# custom_line_V1_mux6.net
KiCad netlist of a schematic drawn in Altium Designer
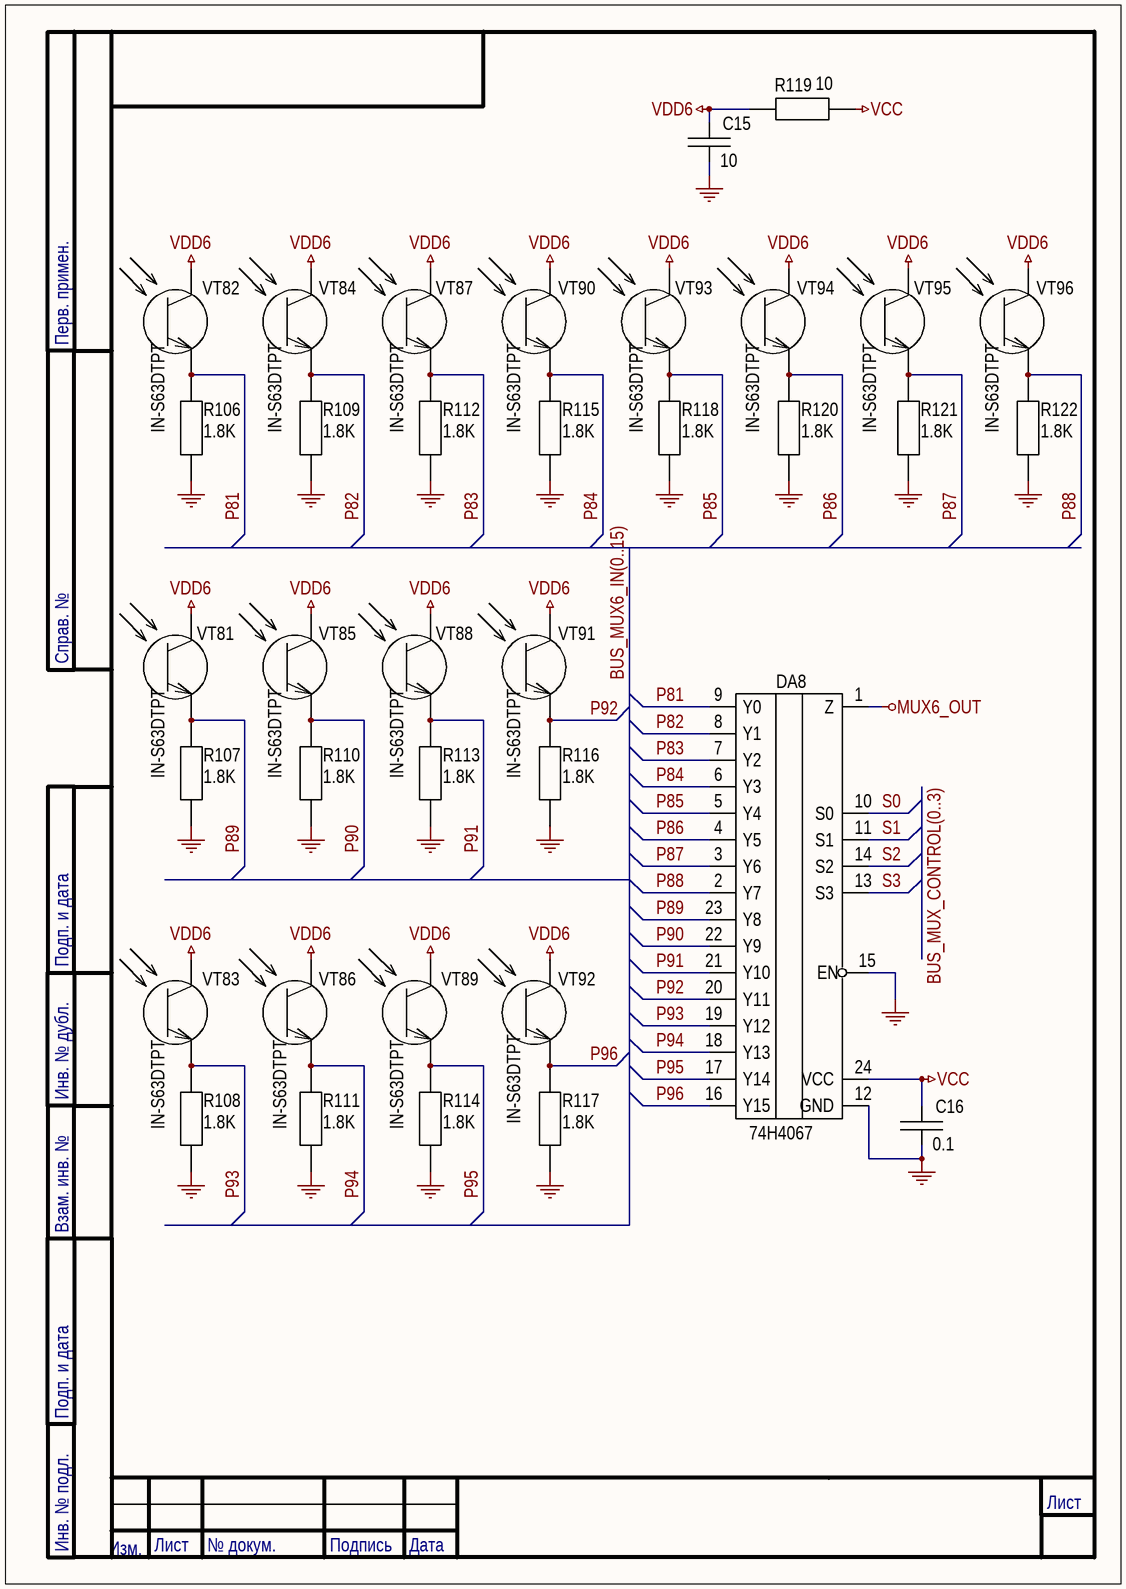
[diagram p0: custom_line_V1_mux6.SchDoc]

(export (version "E")
  (design (tool "Eeschema 10.0.6"))
  (components
    (comp (ref "C15") (value "10") (footprint "CC_0805") (libsource (lib "my_discrete_new") (part "C")))
    (comp (ref "C16") (value "0.1") (footprint "CC_0603") (libsource (lib "my_discrete_new") (part "C")))
    (comp (ref "DA8")
      (value "74HC4067")
      (footprint "TSSOP-24")
      (description "74HC4067PW")
      (fields (field (name "TYPE") "74H4067"))
      (libsource (lib "my_microschems_new") (part "74HCT4067"))
    )
    (comp (ref "R106")
      (value "1.8K")
      (footprint "RC_0603_SMALL")
      (fields (field (name "POWER") "0.125W"))
      (libsource (lib "my_discrete_new") (part "R"))
    )
    (comp (ref "R107")
      (value "1.8K")
      (footprint "RC_0603_SMALL")
      (fields (field (name "POWER") "0.125W"))
      (libsource (lib "my_discrete_new") (part "R"))
    )
    (comp (ref "R108")
      (value "1.8K")
      (footprint "RC_0603_SMALL")
      (fields (field (name "POWER") "0.125W"))
      (libsource (lib "my_discrete_new") (part "R"))
    )
    (comp (ref "R109")
      (value "1.8K")
      (footprint "RC_0603_SMALL")
      (fields (field (name "POWER") "0.125W"))
      (libsource (lib "my_discrete_new") (part "R"))
    )
    (comp (ref "R110")
      (value "1.8K")
      (footprint "RC_0603_SMALL")
      (fields (field (name "POWER") "0.125W"))
      (libsource (lib "my_discrete_new") (part "R"))
    )
    (comp (ref "R111")
      (value "1.8K")
      (footprint "RC_0603_SMALL")
      (fields (field (name "POWER") "0.125W"))
      (libsource (lib "my_discrete_new") (part "R"))
    )
    (comp (ref "R112")
      (value "1.8K")
      (footprint "RC_0603_SMALL")
      (fields (field (name "POWER") "0.125W"))
      (libsource (lib "my_discrete_new") (part "R"))
    )
    (comp (ref "R113")
      (value "1.8K")
      (footprint "RC_0603_SMALL")
      (fields (field (name "POWER") "0.125W"))
      (libsource (lib "my_discrete_new") (part "R"))
    )
    (comp (ref "R114")
      (value "1.8K")
      (footprint "RC_0603_SMALL")
      (fields (field (name "POWER") "0.125W"))
      (libsource (lib "my_discrete_new") (part "R"))
    )
    (comp (ref "R115")
      (value "1.8K")
      (footprint "RC_0603_SMALL")
      (fields (field (name "POWER") "0.125W"))
      (libsource (lib "my_discrete_new") (part "R"))
    )
    (comp (ref "R116")
      (value "1.8K")
      (footprint "RC_0603_SMALL")
      (fields (field (name "POWER") "0.125W"))
      (libsource (lib "my_discrete_new") (part "R"))
    )
    (comp (ref "R117")
      (value "1.8K")
      (footprint "RC_0603_SMALL")
      (fields (field (name "POWER") "0.125W"))
      (libsource (lib "my_discrete_new") (part "R"))
    )
    (comp (ref "R118")
      (value "1.8K")
      (footprint "RC_0603_SMALL")
      (fields (field (name "POWER") "0.125W"))
      (libsource (lib "my_discrete_new") (part "R"))
    )
    (comp (ref "R119")
      (value "10")
      (footprint "RC_0603_SMALL")
      (fields (field (name "POWER") "0.125W"))
      (libsource (lib "my_discrete_new") (part "R"))
    )
    (comp (ref "R120")
      (value "1.8K")
      (footprint "RC_0603_SMALL")
      (fields (field (name "POWER") "0.125W"))
      (libsource (lib "my_discrete_new") (part "R"))
    )
    (comp (ref "R121")
      (value "1.8K")
      (footprint "RC_0603_SMALL")
      (fields (field (name "POWER") "0.125W"))
      (libsource (lib "my_discrete_new") (part "R"))
    )
    (comp (ref "R122")
      (value "1.8K")
      (footprint "RC_0603_SMALL")
      (fields (field (name "POWER") "0.125W"))
      (libsource (lib "my_discrete_new") (part "R"))
    )
    (comp (ref "VT81")
      (value "IN-S63DTPT")
      (footprint "LED_0603")
      (description "Phototransistor (Inolux)")
      (libsource (lib "my_discrete_new") (part "phototransistor"))
    )
    (comp (ref "VT82")
      (value "IN-S63DTPT")
      (footprint "LED_0603")
      (description "Phototransistor (Inolux)")
      (libsource (lib "my_discrete_new") (part "phototransistor"))
    )
    (comp (ref "VT83")
      (value "IN-S63DTPT")
      (footprint "LED_0603")
      (description "Phototransistor (Inolux)")
      (libsource (lib "my_discrete_new") (part "phototransistor"))
    )
    (comp (ref "VT84")
      (value "IN-S63DTPT")
      (footprint "LED_0603")
      (description "Phototransistor (Inolux)")
      (libsource (lib "my_discrete_new") (part "phototransistor"))
    )
    (comp (ref "VT85")
      (value "IN-S63DTPT")
      (footprint "LED_0603")
      (description "Phototransistor (Inolux)")
      (libsource (lib "my_discrete_new") (part "phototransistor"))
    )
    (comp (ref "VT86")
      (value "IN-S63DTPT")
      (footprint "LED_0603")
      (description "Phototransistor (Inolux)")
      (libsource (lib "my_discrete_new") (part "phototransistor"))
    )
    (comp (ref "VT87")
      (value "IN-S63DTPT")
      (footprint "LED_0603")
      (description "Phototransistor (Inolux)")
      (libsource (lib "my_discrete_new") (part "phototransistor"))
    )
    (comp (ref "VT88")
      (value "IN-S63DTPT")
      (footprint "LED_0603")
      (description "Phototransistor (Inolux)")
      (libsource (lib "my_discrete_new") (part "phototransistor"))
    )
    (comp (ref "VT89")
      (value "IN-S63DTPT")
      (footprint "LED_0603")
      (description "Phototransistor (Inolux)")
      (libsource (lib "my_discrete_new") (part "phototransistor"))
    )
    (comp (ref "VT90")
      (value "IN-S63DTPT")
      (footprint "LED_0603")
      (description "Phototransistor (Inolux)")
      (libsource (lib "my_discrete_new") (part "phototransistor"))
    )
    (comp (ref "VT91")
      (value "IN-S63DTPT")
      (footprint "LED_0603")
      (description "Phototransistor (Inolux)")
      (libsource (lib "my_discrete_new") (part "phototransistor"))
    )
    (comp (ref "VT92")
      (value "IN-S63DTPT")
      (footprint "LED_0603")
      (description "Phototransistor (Inolux)")
      (libsource (lib "my_discrete_new") (part "phototransistor"))
    )
    (comp (ref "VT93")
      (value "IN-S63DTPT")
      (footprint "LED_0603")
      (description "Phototransistor (Inolux)")
      (libsource (lib "my_discrete_new") (part "phototransistor"))
    )
    (comp (ref "VT94")
      (value "IN-S63DTPT")
      (footprint "LED_0603")
      (description "Phototransistor (Inolux)")
      (libsource (lib "my_discrete_new") (part "phototransistor"))
    )
    (comp (ref "VT95")
      (value "IN-S63DTPT")
      (footprint "LED_0603")
      (description "Phototransistor (Inolux)")
      (libsource (lib "my_discrete_new") (part "phototransistor"))
    )
    (comp (ref "VT96")
      (value "IN-S63DTPT")
      (footprint "LED_0603")
      (description "Phototransistor (Inolux)")
      (libsource (lib "my_discrete_new") (part "phototransistor"))
    )
  )
  (nets
    (net (code "3") (name "/P81") (class "Default")
      (node (ref "DA8") (pin "9") (pinfunction "Y0_9") (pintype "passive"))
      (node (ref "R106") (pin "2") (pinfunction "2_2") (pintype "passive"))
      (node (ref "VT82") (pin "2") (pinfunction "E_2") (pintype "passive"))
    )
    (net (code "4") (name "/P82") (class "Default")
      (node (ref "DA8") (pin "8") (pinfunction "Y1_8") (pintype "passive"))
      (node (ref "R109") (pin "2") (pinfunction "2_2") (pintype "passive"))
      (node (ref "VT84") (pin "2") (pinfunction "E_2") (pintype "passive"))
    )
    (net (code "5") (name "/P83") (class "Default")
      (node (ref "DA8") (pin "7") (pinfunction "Y2_7") (pintype "passive"))
      (node (ref "R112") (pin "2") (pinfunction "2_2") (pintype "passive"))
      (node (ref "VT87") (pin "2") (pinfunction "E_2") (pintype "passive"))
    )
    (net (code "6") (name "/P84") (class "Default")
      (node (ref "DA8") (pin "6") (pinfunction "Y3_6") (pintype "passive"))
      (node (ref "R115") (pin "2") (pinfunction "2_2") (pintype "passive"))
      (node (ref "VT90") (pin "2") (pinfunction "E_2") (pintype "passive"))
    )
    (net (code "7") (name "/P85") (class "Default")
      (node (ref "DA8") (pin "5") (pinfunction "Y4_5") (pintype "passive"))
      (node (ref "R118") (pin "2") (pinfunction "2_2") (pintype "passive"))
      (node (ref "VT93") (pin "2") (pinfunction "E_2") (pintype "passive"))
    )
    (net (code "8") (name "/P86") (class "Default")
      (node (ref "DA8") (pin "4") (pinfunction "Y5_4") (pintype "passive"))
      (node (ref "R120") (pin "2") (pinfunction "2_2") (pintype "passive"))
      (node (ref "VT94") (pin "2") (pinfunction "E_2") (pintype "passive"))
    )
    (net (code "9") (name "/P87") (class "Default")
      (node (ref "DA8") (pin "3") (pinfunction "Y6_3") (pintype "passive"))
      (node (ref "R121") (pin "2") (pinfunction "2_2") (pintype "passive"))
      (node (ref "VT95") (pin "2") (pinfunction "E_2") (pintype "passive"))
    )
    (net (code "10") (name "/P88") (class "Default")
      (node (ref "DA8") (pin "2") (pinfunction "Y7_2") (pintype "passive"))
      (node (ref "R122") (pin "2") (pinfunction "2_2") (pintype "passive"))
      (node (ref "VT96") (pin "2") (pinfunction "E_2") (pintype "passive"))
    )
    (net (code "11") (name "/P89") (class "Default")
      (node (ref "DA8") (pin "23") (pinfunction "Y8_23") (pintype "passive"))
      (node (ref "R107") (pin "2") (pinfunction "2_2") (pintype "passive"))
      (node (ref "VT81") (pin "2") (pinfunction "E_2") (pintype "passive"))
    )
    (net (code "12") (name "/P90") (class "Default")
      (node (ref "DA8") (pin "22") (pinfunction "Y9_22") (pintype "passive"))
      (node (ref "R110") (pin "2") (pinfunction "2_2") (pintype "passive"))
      (node (ref "VT85") (pin "2") (pinfunction "E_2") (pintype "passive"))
    )
    (net (code "13") (name "/P91") (class "Default")
      (node (ref "DA8") (pin "21") (pinfunction "Y10_21") (pintype "passive"))
      (node (ref "R113") (pin "2") (pinfunction "2_2") (pintype "passive"))
      (node (ref "VT88") (pin "2") (pinfunction "E_2") (pintype "passive"))
    )
    (net (code "14") (name "/P92") (class "Default")
      (node (ref "DA8") (pin "20") (pinfunction "Y11_20") (pintype "passive"))
      (node (ref "R116") (pin "2") (pinfunction "2_2") (pintype "passive"))
      (node (ref "VT91") (pin "2") (pinfunction "E_2") (pintype "passive"))
    )
    (net (code "15") (name "/P93") (class "Default")
      (node (ref "DA8") (pin "19") (pinfunction "Y12_19") (pintype "passive"))
      (node (ref "R108") (pin "2") (pinfunction "2_2") (pintype "passive"))
      (node (ref "VT83") (pin "2") (pinfunction "E_2") (pintype "passive"))
    )
    (net (code "16") (name "/P94") (class "Default")
      (node (ref "DA8") (pin "18") (pinfunction "Y13_18") (pintype "passive"))
      (node (ref "R111") (pin "2") (pinfunction "2_2") (pintype "passive"))
      (node (ref "VT86") (pin "2") (pinfunction "E_2") (pintype "passive"))
    )
    (net (code "17") (name "/P95") (class "Default")
      (node (ref "DA8") (pin "17") (pinfunction "Y14_17") (pintype "passive"))
      (node (ref "R114") (pin "2") (pinfunction "2_2") (pintype "passive"))
      (node (ref "VT89") (pin "2") (pinfunction "E_2") (pintype "passive"))
    )
    (net (code "18") (name "/P96") (class "Default")
      (node (ref "DA8") (pin "16") (pinfunction "Y15_16") (pintype "passive"))
      (node (ref "R117") (pin "2") (pinfunction "2_2") (pintype "passive"))
      (node (ref "VT92") (pin "2") (pinfunction "E_2") (pintype "passive"))
    )
    (net (code "19") (name "/S0") (class "Default")
      (node (ref "DA8") (pin "10") (pinfunction "S0_10") (pintype "passive"))
    )
    (net (code "20") (name "/S1") (class "Default")
      (node (ref "DA8") (pin "11") (pinfunction "S1_11") (pintype "passive"))
    )
    (net (code "21") (name "/S2") (class "Default")
      (node (ref "DA8") (pin "14") (pinfunction "S2_14") (pintype "passive"))
    )
    (net (code "22") (name "/S3") (class "Default")
      (node (ref "DA8") (pin "13") (pinfunction "S3_13") (pintype "passive"))
    )
    (net (code "25") (name "GND") (class "Default")
      (node (ref "C15") (pin "1") (pinfunction "1_1") (pintype "passive"))
      (node (ref "C16") (pin "1") (pinfunction "1_1") (pintype "passive"))
      (node (ref "DA8") (pin "12") (pinfunction "GND_12") (pintype "power_in"))
      (node (ref "DA8") (pin "15") (pinfunction "EN_15") (pintype "passive"))
      (node (ref "R106") (pin "1") (pinfunction "1_1") (pintype "passive"))
      (node (ref "R107") (pin "1") (pinfunction "1_1") (pintype "passive"))
      (node (ref "R108") (pin "1") (pinfunction "1_1") (pintype "passive"))
      (node (ref "R109") (pin "1") (pinfunction "1_1") (pintype "passive"))
      (node (ref "R110") (pin "1") (pinfunction "1_1") (pintype "passive"))
      (node (ref "R111") (pin "1") (pinfunction "1_1") (pintype "passive"))
      (node (ref "R112") (pin "1") (pinfunction "1_1") (pintype "passive"))
      (node (ref "R113") (pin "1") (pinfunction "1_1") (pintype "passive"))
      (node (ref "R114") (pin "1") (pinfunction "1_1") (pintype "passive"))
      (node (ref "R115") (pin "1") (pinfunction "1_1") (pintype "passive"))
      (node (ref "R116") (pin "1") (pinfunction "1_1") (pintype "passive"))
      (node (ref "R117") (pin "1") (pinfunction "1_1") (pintype "passive"))
      (node (ref "R118") (pin "1") (pinfunction "1_1") (pintype "passive"))
      (node (ref "R120") (pin "1") (pinfunction "1_1") (pintype "passive"))
      (node (ref "R121") (pin "1") (pinfunction "1_1") (pintype "passive"))
      (node (ref "R122") (pin "1") (pinfunction "1_1") (pintype "passive"))
    )
    (net (code "26") (name "MUX6_OUT") (class "Default")
      (node (ref "DA8") (pin "1") (pinfunction "Z_1") (pintype "passive"))
    )
    (net (code "27") (name "VCC") (class "Default")
      (node (ref "C16") (pin "2") (pinfunction "2_2") (pintype "passive"))
      (node (ref "DA8") (pin "24") (pinfunction "VCC_24") (pintype "power_in"))
      (node (ref "R119") (pin "1") (pinfunction "1_1") (pintype "passive"))
    )
    (net (code "28") (name "VDD6") (class "Default")
      (node (ref "C15") (pin "2") (pinfunction "2_2") (pintype "passive"))
      (node (ref "R119") (pin "2") (pinfunction "2_2") (pintype "passive"))
      (node (ref "VT81") (pin "1") (pinfunction "C_1") (pintype "passive"))
      (node (ref "VT82") (pin "1") (pinfunction "C_1") (pintype "passive"))
      (node (ref "VT83") (pin "1") (pinfunction "C_1") (pintype "passive"))
      (node (ref "VT84") (pin "1") (pinfunction "C_1") (pintype "passive"))
      (node (ref "VT85") (pin "1") (pinfunction "C_1") (pintype "passive"))
      (node (ref "VT86") (pin "1") (pinfunction "C_1") (pintype "passive"))
      (node (ref "VT87") (pin "1") (pinfunction "C_1") (pintype "passive"))
      (node (ref "VT88") (pin "1") (pinfunction "C_1") (pintype "passive"))
      (node (ref "VT89") (pin "1") (pinfunction "C_1") (pintype "passive"))
      (node (ref "VT90") (pin "1") (pinfunction "C_1") (pintype "passive"))
      (node (ref "VT91") (pin "1") (pinfunction "C_1") (pintype "passive"))
      (node (ref "VT92") (pin "1") (pinfunction "C_1") (pintype "passive"))
      (node (ref "VT93") (pin "1") (pinfunction "C_1") (pintype "passive"))
      (node (ref "VT94") (pin "1") (pinfunction "C_1") (pintype "passive"))
      (node (ref "VT95") (pin "1") (pinfunction "C_1") (pintype "passive"))
      (node (ref "VT96") (pin "1") (pinfunction "C_1") (pintype "passive"))
    )
  )
)
